# Qwiic_Glove.net
KiCad netlist of a schematic drawn in EAGLE
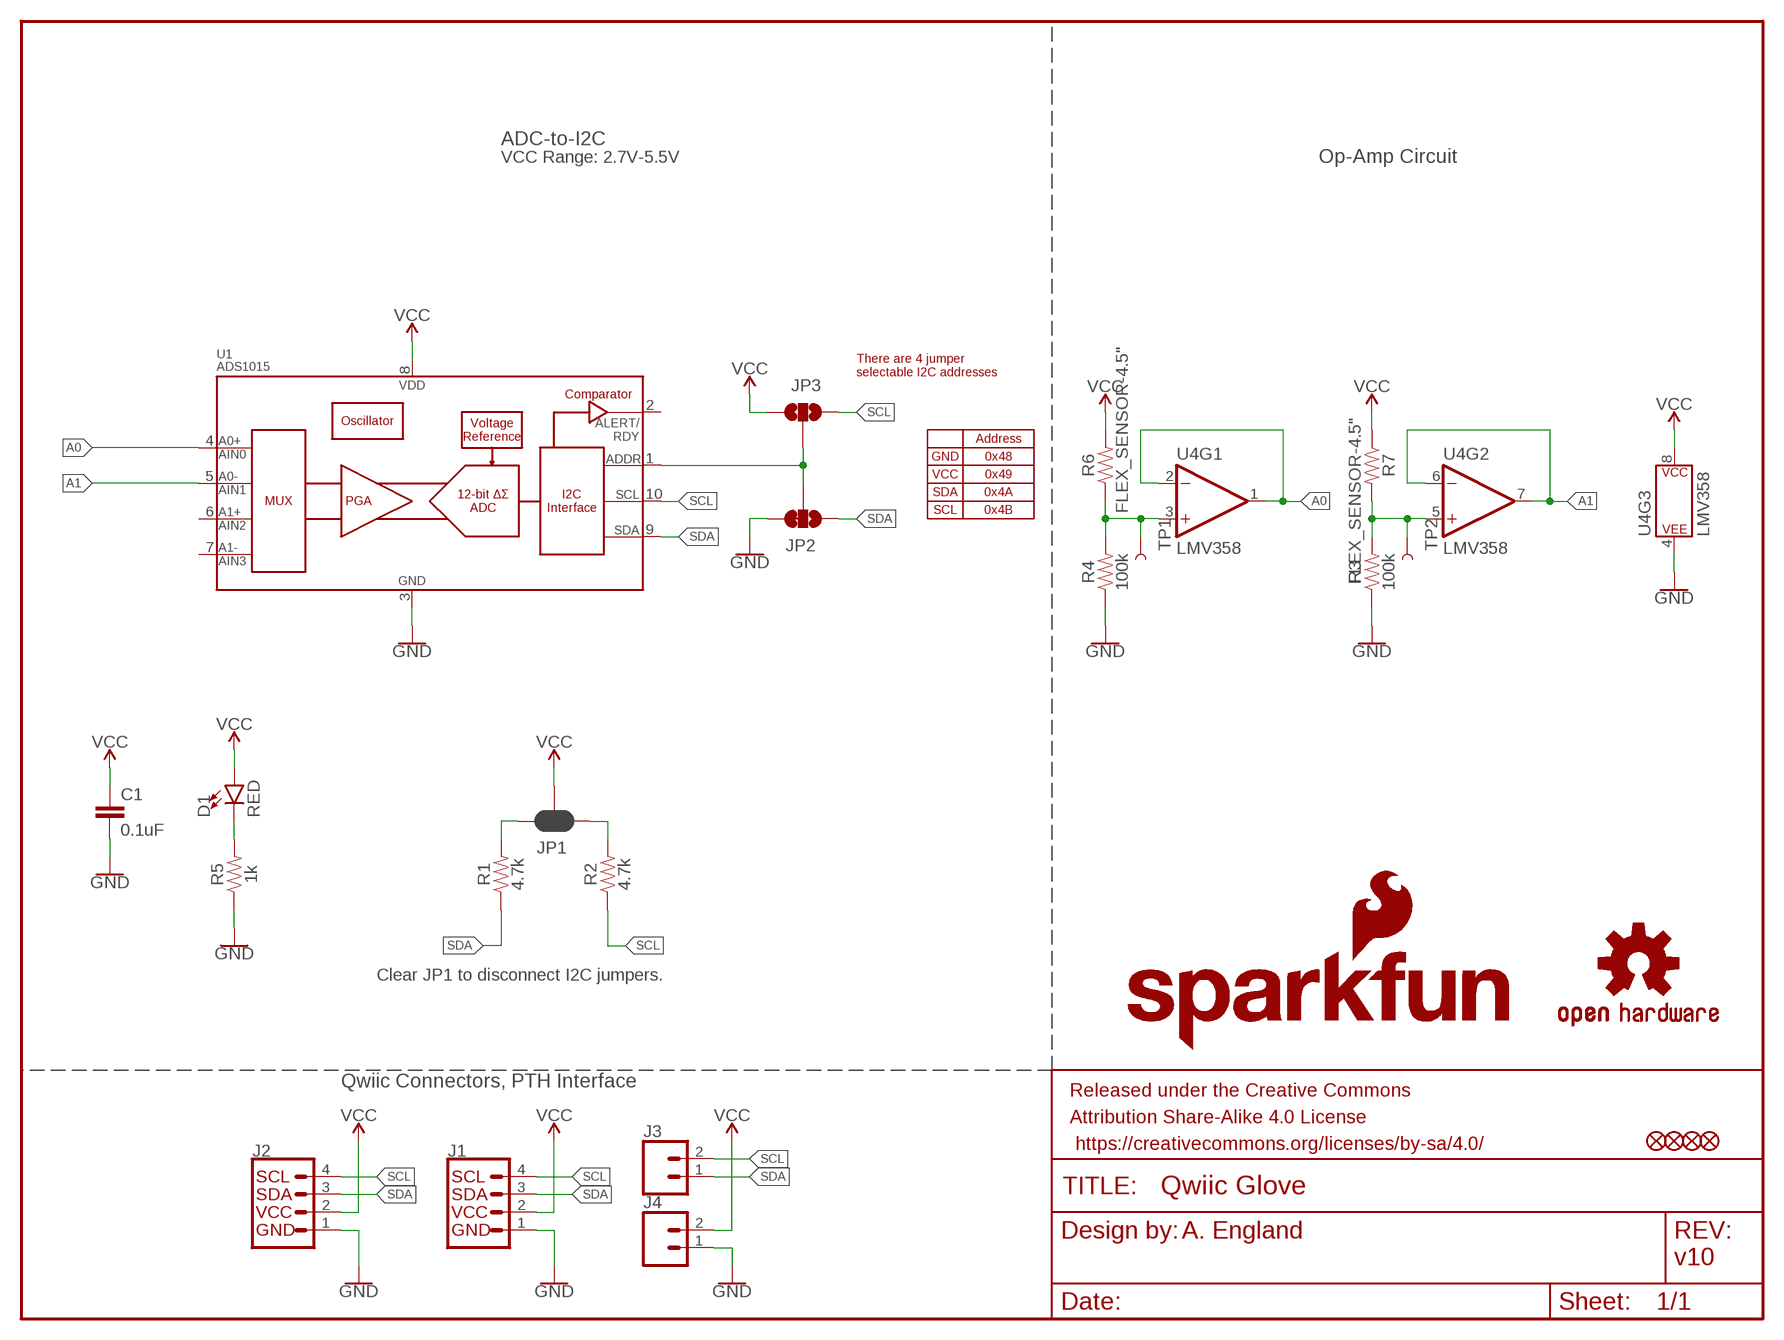
[diagram p0: schematic, sheet 1]

(export (version "E")
  (design (tool "Eeschema 10.0.6"))
  (components
    (comp (ref "C1")
      (value "0.1uF")
      (footprint "eagle-import:0603")
      (libsource (lib "eagle-import") (part "0.1UF-0603-25V-(+80/-20%)"))
    )
    (comp (ref "D1")
      (value "RED")
      (footprint "eagle-import:LED-0603")
      (libsource (lib "eagle-import") (part "LED-RED0603"))
    )
    (comp (ref "FD1")
      (value "FIDUCIALUFIDUCIAL")
      (footprint "eagle-import:FIDUCIAL-MICRO")
      (libsource (lib "eagle-import") (part "FIDUCIALUFIDUCIAL"))
    )
    (comp (ref "FD2")
      (value "FIDUCIALUFIDUCIAL")
      (footprint "eagle-import:FIDUCIAL-MICRO")
      (libsource (lib "eagle-import") (part "FIDUCIALUFIDUCIAL"))
    )
    (comp (ref "FD3")
      (value "FIDUCIALUFIDUCIAL")
      (footprint "eagle-import:FIDUCIAL-MICRO")
      (libsource (lib "eagle-import") (part "FIDUCIALUFIDUCIAL"))
    )
    (comp (ref "FD4")
      (value "FIDUCIALUFIDUCIAL")
      (footprint "eagle-import:FIDUCIAL-MICRO")
      (libsource (lib "eagle-import") (part "FIDUCIALUFIDUCIAL"))
    )
    (comp (ref "FRAME1")
      (value "FRAME-LETTER")
      (footprint "eagle-import:CREATIVE_COMMONS")
      (libsource (lib "eagle-import") (part "FRAME-LETTER"))
    )
    (comp (ref "J1")
      (value "QWIIC_CONNECTORJS-1MM")
      (footprint "eagle-import:1X04_1MM_RA")
      (libsource (lib "eagle-import") (part "QWIIC_CONNECTORJS-1MM"))
    )
    (comp (ref "J2")
      (value "QWIIC_CONNECTORJS-1MM")
      (footprint "eagle-import:1X04_1MM_RA")
      (libsource (lib "eagle-import") (part "QWIIC_CONNECTORJS-1MM"))
    )
    (comp (ref "J3")
      (value "CONN_02")
      (footprint "eagle-import:1X02")
      (libsource (lib "eagle-import") (part "CONN_02"))
    )
    (comp (ref "J4")
      (value "CONN_02")
      (footprint "eagle-import:1X02")
      (libsource (lib "eagle-import") (part "CONN_02"))
    )
    (comp (ref "JP1")
      (value "JUMPER-SMT_3_2-NC_PASTE_NO-SILK")
      (footprint "eagle-import:SMT-JUMPER_3_2-NC_PASTE_NO-SILK")
      (libsource (lib "eagle-import") (part "JUMPER-SMT_3_2-NC_PASTE_NO-SILK"))
    )
    (comp (ref "JP2")
      (value "JUMPER-SMT_3_1-NC_TRACE_NO-SILK")
      (footprint "eagle-import:SMT-JUMPER_3_1-NC_TRACE_NO-SILK")
      (libsource (lib "eagle-import") (part "JUMPER-SMT_3_1-NC_TRACE_NO-SILK"))
    )
    (comp (ref "JP3")
      (value "JUMPER-SMT_3_NO_NO_SILK")
      (footprint "eagle-import:SMT-JUMPER_3_0-NO_TRACE_NO-SILK")
      (libsource (lib "eagle-import") (part "JUMPER-SMT_3_NO_NO_SILK"))
    )
    (comp (ref "LOGO1")
      (value "SFE_LOGO_NAME_FLAME.1_INCH")
      (footprint "eagle-import:SFE_LOGO_NAME_FLAME_.1")
      (libsource (lib "eagle-import") (part "SFE_LOGO_NAME_FLAME.1_INCH"))
    )
    (comp (ref "LOGO2")
      (value "OSHW-LOGOS")
      (footprint "eagle-import:OSHW-LOGO-S")
      (libsource (lib "eagle-import") (part "OSHW-LOGOS"))
    )
    (comp (ref "LOGO3")
      (value "SFE_LOGO_FLAME.1_INCH")
      (footprint "eagle-import:SFE_LOGO_FLAME_.1")
      (libsource (lib "eagle-import") (part "SFE_LOGO_FLAME.1_INCH"))
    )
    (comp (ref "R1")
      (value "4.7k")
      (footprint "eagle-import:0603")
      (libsource (lib "eagle-import") (part "4.7KOHM-0603-1/10W-1%"))
    )
    (comp (ref "R2")
      (value "4.7k")
      (footprint "eagle-import:0603")
      (libsource (lib "eagle-import") (part "4.7KOHM-0603-1/10W-1%"))
    )
    (comp (ref "R3")
      (value "100k")
      (footprint "eagle-import:0603")
      (libsource (lib "eagle-import") (part "100KOHM-0603-1/10W-1%"))
    )
    (comp (ref "R4")
      (value "100k")
      (footprint "eagle-import:0603")
      (libsource (lib "eagle-import") (part "100KOHM-0603-1/10W-1%"))
    )
    (comp (ref "R5")
      (value "1k")
      (footprint "eagle-import:0603")
      (libsource (lib "eagle-import") (part "1KOHM-0603-1/10W-1%"))
    )
    (comp (ref "R6")
      (value "FLEX_SENSOR-4.5\"")
      (footprint "eagle-import:FLEX_SENSOR")
      (libsource (lib "eagle-import") (part "FLEX_SENSOR-4.5{dblquote}"))
    )
    (comp (ref "R7")
      (value "FLEX_SENSOR-4.5\"")
      (footprint "eagle-import:FLEX_SENSOR")
      (libsource (lib "eagle-import") (part "FLEX_SENSOR-4.5{dblquote}"))
    )
    (comp (ref "TP1")
      (value "TEST-POINT3")
      (footprint "eagle-import:PAD.03X.03")
      (libsource (lib "eagle-import") (part "TEST-POINT3"))
    )
    (comp (ref "TP2")
      (value "TEST-POINT3")
      (footprint "eagle-import:PAD.03X.03")
      (libsource (lib "eagle-import") (part "TEST-POINT3"))
    )
    (comp (ref "U1")
      (value "ADS1015")
      (footprint "eagle-import:MSOP10")
      (libsource (lib "eagle-import") (part "ADS1015"))
    )
    (comp (ref "U4")
      (value "LMV358")
      (footprint "eagle-import:SO08")
      (libsource (lib "eagle-import") (part "LMV358SOIC"))
    )
  )
  (nets
    (net (code "1") (name "A0") (class "Default")
      (node (ref "U1") (pin "4") (pinfunction "AIN0_4") (pintype "bidirectional"))
      (node (ref "U4") (pin "1") (pinfunction "OUT_1") (pintype "output"))
      (node (ref "U4") (pin "2") (pinfunction "-IN_2") (pintype "input"))
    )
    (net (code "2") (name "A1") (class "Default")
      (node (ref "U1") (pin "5") (pinfunction "AIN1_5") (pintype "bidirectional"))
      (node (ref "U4") (pin "6") (pinfunction "-IN_6") (pintype "input"))
      (node (ref "U4") (pin "7") (pinfunction "OUT_7") (pintype "output"))
    )
    (net (code "3") (name "GND") (class "Default")
      (node (ref "C1") (pin "2") (pinfunction "2_2") (pintype "passive"))
      (node (ref "J1") (pin "1") (pinfunction "1_1") (pintype "power_in"))
      (node (ref "J2") (pin "1") (pinfunction "1_1") (pintype "power_in"))
      (node (ref "J4") (pin "1") (pinfunction "1_1") (pintype "passive"))
      (node (ref "JP2") (pin "3") (pinfunction "3_3") (pintype "passive"))
      (node (ref "R3") (pin "1") (pinfunction "1_1") (pintype "passive"))
      (node (ref "R4") (pin "1") (pinfunction "1_1") (pintype "passive"))
      (node (ref "R5") (pin "1") (pinfunction "1_1") (pintype "passive"))
      (node (ref "U1") (pin "3") (pinfunction "VSS_3") (pintype "bidirectional"))
      (node (ref "U4") (pin "4") (pinfunction "P$V-_4") (pintype "bidirectional"))
    )
    (net (code "4") (name "Net-(D1-PadC)") (class "Default")
      (node (ref "D1") (pin "C") (pinfunction "C_C") (pintype "passive"))
      (node (ref "R5") (pin "2") (pinfunction "2_2") (pintype "passive"))
    )
    (net (code "5") (name "Net-(JP1-Pad1)") (class "Default")
      (node (ref "JP1") (pin "1") (pinfunction "1_1") (pintype "passive"))
      (node (ref "R2") (pin "2") (pinfunction "2_2") (pintype "passive"))
    )
    (net (code "6") (name "Net-(JP1-Pad3)") (class "Default")
      (node (ref "JP1") (pin "3") (pinfunction "3_3") (pintype "passive"))
      (node (ref "R1") (pin "2") (pinfunction "2_2") (pintype "passive"))
    )
    (net (code "7") (name "Net-(R6-1)") (class "Default")
      (node (ref "R4") (pin "2") (pinfunction "2_2") (pintype "passive"))
      (node (ref "R6") (pin "P$1") (pinfunction "1_P$1") (pintype "passive"))
      (node (ref "TP1") (pin "P$1") (pinfunction "1_P$1") (pintype "bidirectional"))
      (node (ref "U4") (pin "3") (pinfunction "+IN_3") (pintype "input"))
    )
    (net (code "8") (name "Net-(R7-2)") (class "Default")
      (node (ref "R3") (pin "2") (pinfunction "2_2") (pintype "passive"))
      (node (ref "R7") (pin "P$2") (pinfunction "2_P$2") (pintype "passive"))
      (node (ref "TP2") (pin "P$1") (pinfunction "1_P$1") (pintype "bidirectional"))
      (node (ref "U4") (pin "5") (pinfunction "+IN_5") (pintype "input"))
    )
    (net (code "9") (name "Net-(U1-ADDR)") (class "Default")
      (node (ref "JP2") (pin "2") (pinfunction "2_2") (pintype "passive"))
      (node (ref "JP3") (pin "2") (pinfunction "2_2") (pintype "passive"))
      (node (ref "U1") (pin "1") (pinfunction "ADDR_1") (pintype "bidirectional"))
    )
    (net (code "10") (name "SCL") (class "Default")
      (node (ref "J1") (pin "4") (pinfunction "4_4") (pintype "passive"))
      (node (ref "J2") (pin "4") (pinfunction "4_4") (pintype "passive"))
      (node (ref "J3") (pin "2") (pinfunction "2_2") (pintype "passive"))
      (node (ref "JP3") (pin "3") (pinfunction "3_3") (pintype "passive"))
      (node (ref "R2") (pin "1") (pinfunction "1_1") (pintype "passive"))
      (node (ref "U1") (pin "10") (pinfunction "SCL_10") (pintype "bidirectional"))
    )
    (net (code "11") (name "SDA") (class "Default")
      (node (ref "J1") (pin "3") (pinfunction "3_3") (pintype "passive"))
      (node (ref "J2") (pin "3") (pinfunction "3_3") (pintype "passive"))
      (node (ref "J3") (pin "1") (pinfunction "1_1") (pintype "passive"))
      (node (ref "JP2") (pin "1") (pinfunction "1_1") (pintype "passive"))
      (node (ref "R1") (pin "1") (pinfunction "1_1") (pintype "passive"))
      (node (ref "U1") (pin "9") (pinfunction "SDA_9") (pintype "bidirectional"))
    )
    (net (code "12") (name "VCC") (class "Default")
      (node (ref "C1") (pin "1") (pinfunction "1_1") (pintype "passive"))
      (node (ref "D1") (pin "A") (pinfunction "A_A") (pintype "passive"))
      (node (ref "J1") (pin "2") (pinfunction "2_2") (pintype "power_in"))
      (node (ref "J2") (pin "2") (pinfunction "2_2") (pintype "power_in"))
      (node (ref "J4") (pin "2") (pinfunction "2_2") (pintype "passive"))
      (node (ref "JP1") (pin "2") (pinfunction "2_2") (pintype "passive"))
      (node (ref "JP3") (pin "1") (pinfunction "1_1") (pintype "passive"))
      (node (ref "R6") (pin "P$2") (pinfunction "2_P$2") (pintype "passive"))
      (node (ref "R7") (pin "P$1") (pinfunction "1_P$1") (pintype "passive"))
      (node (ref "U1") (pin "8") (pinfunction "VDD_8") (pintype "bidirectional"))
      (node (ref "U4") (pin "8") (pinfunction "P$V+_8") (pintype "bidirectional"))
    )
    (net (code "13") (name "unconnected-(U1-AIN2-Pad6)") (class "Default")
      (node (ref "U1") (pin "6") (pinfunction "AIN2_6") (pintype "bidirectional"))
    )
    (net (code "14") (name "unconnected-(U1-AIN3-Pad7)") (class "Default")
      (node (ref "U1") (pin "7") (pinfunction "AIN3_7") (pintype "bidirectional"))
    )
    (net (code "15") (name "unconnected-(U1-ALERT{slash}RDY-Pad2)") (class "Default")
      (node (ref "U1") (pin "2") (pinfunction "ALERT/RDY_2") (pintype "bidirectional"))
    )
  )
)
